# RiskChemi_Monitor_V1_05M1.net
KiCad netlist of a schematic drawn in Altium Designer
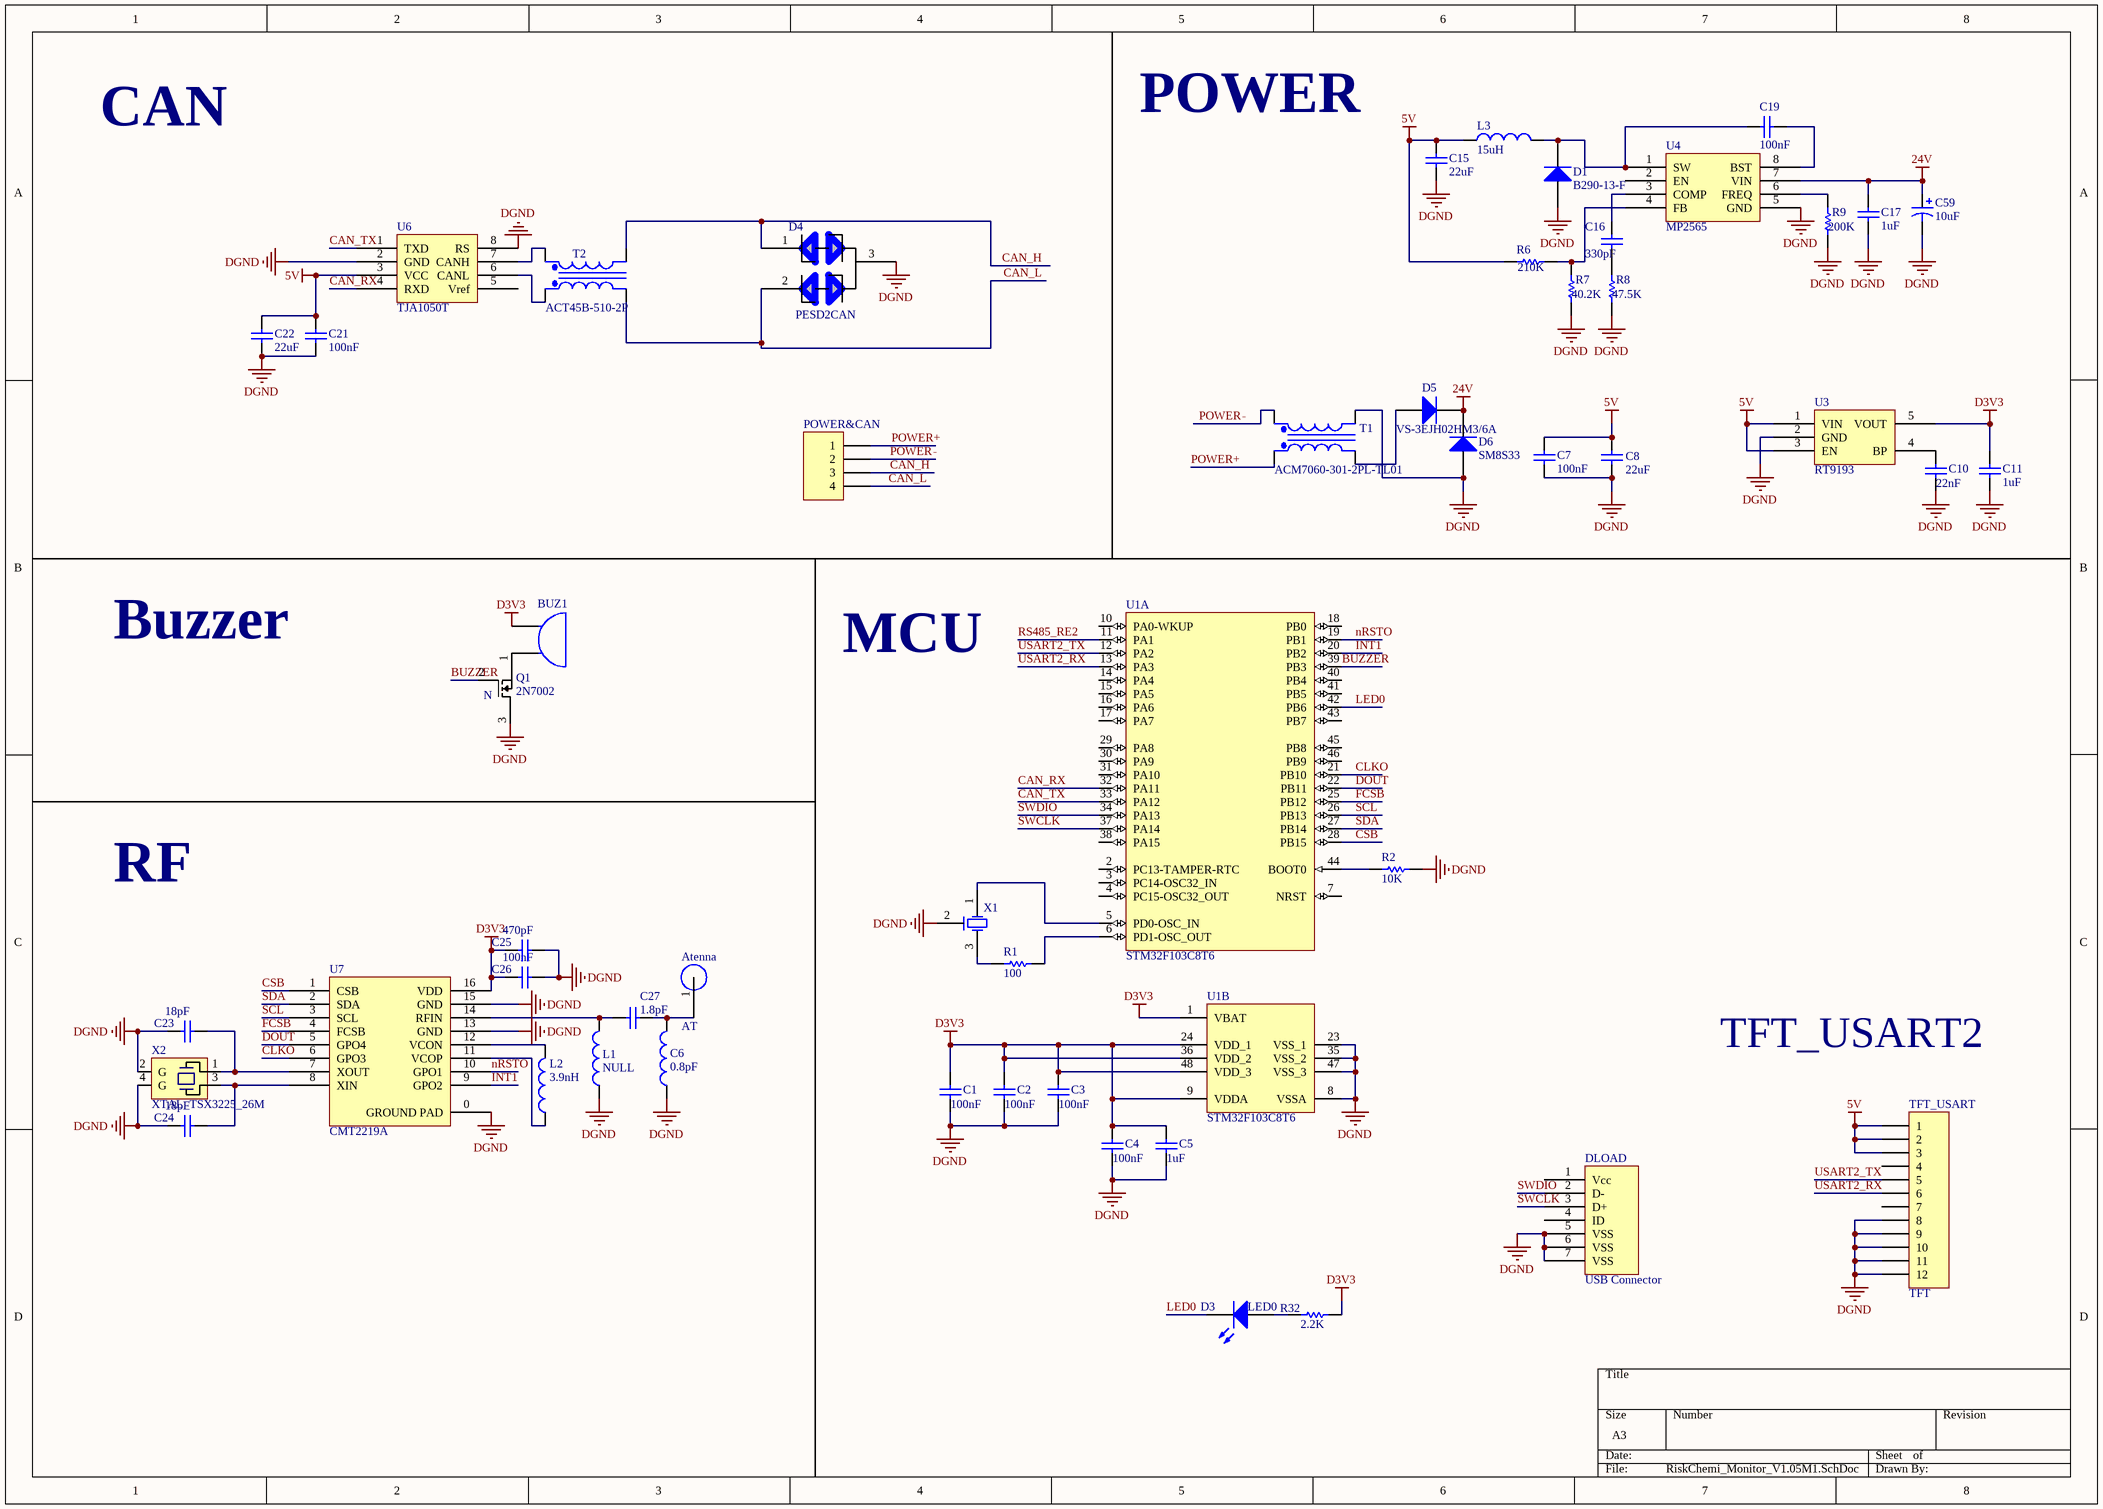
[diagram p0: RiskChemi_Monitor_V1.05M1.SchDoc]

(export (version "E")
  (design (tool "Eeschema 10.0.6"))
  (components
    (comp (ref "Atenna") (value "AT") (footprint "433MHz Atenna") (libsource (lib "MySchlib1") (part "AT")))
    (comp (ref "BUZ1")
      (value "BUZZER")
      (footprint "BUZ0905")
      (description "Buzzer")
      (libsource (lib "杂元件库") (part "BUZZER"))
    )
    (comp (ref "C1")
      (value "100nF")
      (footprint "0603")
      (description "Capacitor")
      (fields (field (name "PUBLISHER") "Altium Limited"))
      (libsource (lib "Miscellaneous Devices") (part "Cap"))
    )
    (comp (ref "C2")
      (value "100nF")
      (footprint "0603")
      (description "Capacitor")
      (fields (field (name "PUBLISHER") "Altium Limited"))
      (libsource (lib "Miscellaneous Devices") (part "Cap"))
    )
    (comp (ref "C3")
      (value "100nF")
      (footprint "0603")
      (description "Capacitor")
      (fields (field (name "PUBLISHER") "Altium Limited"))
      (libsource (lib "Miscellaneous Devices") (part "Cap"))
    )
    (comp (ref "C4")
      (value "100nF")
      (footprint "0603")
      (description "Capacitor")
      (fields (field (name "PUBLISHER") "Altium Limited"))
      (libsource (lib "Miscellaneous Devices") (part "Cap"))
    )
    (comp (ref "C5")
      (value "1uF")
      (footprint "0603")
      (description "Capacitor")
      (fields (field (name "PUBLISHER") "Altium Limited"))
      (libsource (lib "Miscellaneous Devices") (part "Cap"))
    )
    (comp (ref "C6")
      (value "0.8pF")
      (footprint "Miscellaneous Devices:0402")
      (description "Inductor")
      (fields (field (name "PUBLISHER") "Altium Limited"))
      (libsource (lib "Miscellaneous Devices") (part "Inductor"))
    )
    (comp (ref "C7")
      (value "100nF")
      (footprint "0805")
      (description "Capacitor,100V")
      (fields (field (name "PUBLISHER") "Altium Limited"))
      (libsource (lib "Miscellaneous Devices") (part "Cap"))
    )
    (comp (ref "C8")
      (value "22uF")
      (footprint "0805")
      (description "Capacitor")
      (fields (field (name "PUBLISHER") "Altium Limited"))
      (libsource (lib "Miscellaneous Devices") (part "Cap"))
    )
    (comp (ref "C10")
      (value "22nF")
      (footprint "BinFeng:0603")
      (description "Capacitor")
      (fields (field (name "PUBLISHER") "Altium Limited"))
      (libsource (lib "Miscellaneous Devices") (part "Cap"))
    )
    (comp (ref "C11")
      (value "1uF")
      (footprint "BinFeng:0603")
      (description "Capacitor")
      (fields (field (name "PUBLISHER") "Altium Limited"))
      (libsource (lib "Miscellaneous Devices") (part "Cap"))
    )
    (comp (ref "C15")
      (value "22uF")
      (footprint "0805")
      (description "Capacitor,50V")
      (fields (field (name "PUBLISHER") "Altium Limited"))
      (libsource (lib "Miscellaneous Devices") (part "Cap"))
    )
    (comp (ref "C16")
      (value "330pF")
      (footprint "BinFeng:0402")
      (description "Capacitor")
      (fields (field (name "PUBLISHER") "Altium Limited"))
      (libsource (lib "Miscellaneous Devices") (part "Cap"))
    )
    (comp (ref "C17")
      (value "1uF")
      (footprint "0805")
      (description "Capacitor,100V")
      (fields (field (name "PUBLISHER") "Altium Limited"))
      (libsource (lib "Miscellaneous Devices") (part "Cap"))
    )
    (comp (ref "C19")
      (value "100nF")
      (footprint "BinFeng:0402")
      (description "Capacitor")
      (fields (field (name "PUBLISHER") "Altium Limited"))
      (libsource (lib "Miscellaneous Devices") (part "Cap"))
    )
    (comp (ref "C21")
      (value "100nF")
      (footprint "0603")
      (description "Capacitor")
      (fields (field (name "PUBLISHER") "Altium Limited"))
      (libsource (lib "Miscellaneous Devices") (part "Cap"))
    )
    (comp (ref "C22")
      (value "22uF")
      (footprint "0805")
      (description "Capacitor")
      (fields (field (name "PUBLISHER") "Altium Limited"))
      (libsource (lib "Miscellaneous Devices") (part "Cap"))
    )
    (comp (ref "C23")
      (value "18pF")
      (footprint "BinFeng:0402")
      (description "Capacitor")
      (fields (field (name "PUBLISHER") "Altium Limited"))
      (libsource (lib "Miscellaneous Devices") (part "Cap"))
    )
    (comp (ref "C24")
      (value "18pF")
      (footprint "BinFeng:0402")
      (description "Capacitor")
      (fields (field (name "PUBLISHER") "Altium Limited"))
      (libsource (lib "Miscellaneous Devices") (part "Cap"))
    )
    (comp (ref "C25")
      (value "470pF")
      (footprint "BinFeng:0402")
      (description "Capacitor")
      (fields (field (name "PUBLISHER") "Altium Limited"))
      (libsource (lib "Miscellaneous Devices") (part "Cap"))
    )
    (comp (ref "C26")
      (value "100nF")
      (footprint "BinFeng:0603")
      (description "Capacitor")
      (fields (field (name "PUBLISHER") "Altium Limited"))
      (libsource (lib "Miscellaneous Devices") (part "Cap"))
    )
    (comp (ref "C27")
      (value "1.8pF")
      (footprint "BinFeng:nosilk_0402")
      (description "Capacitor")
      (fields (field (name "PUBLISHER") "Altium Limited"))
      (libsource (lib "Miscellaneous Devices") (part "Cap"))
    )
    (comp (ref "C59")
      (value "10uF")
      (footprint "6032_pol")
      (description "Polarized Capacitor (Radial)")
      (fields (field (name "PUBLISHER") "Altium Limited"))
      (libsource (lib "Miscellaneous Devices") (part "Cap Pol1"))
    )
    (comp (ref "D1")
      (value "B290-13-F")
      (footprint "back:B290")
      (description "Default Diode")
      (fields (field (name "PUBLISHER") "Altium Limited"))
      (libsource (lib "Miscellaneous Devices") (part "Diode"))
    )
    (comp (ref "D3")
      (value "LED0")
      (footprint "LED")
      (description "green LED")
      (fields (field (name "PUBLISHER") "Altium Limited"))
      (libsource (lib "Miscellaneous Devices") (part "LED0"))
    )
    (comp (ref "D4")
      (value "PESD2CAN")
      (footprint "SOT23")
      (libsource (lib "BinFeng_Connectors") (part "PESD1CAN"))
    )
    (comp (ref "D5")
      (value "VS-3EJH02HM3/6A")
      (footprint "back:B290")
      (description "1 Amp General Purpose Rectifier")
      (fields (field (name "PUBLISHER") "Altium Limited"))
      (libsource (lib "Miscellaneous Devices") (part "Diode 1N4007"))
    )
    (comp (ref "D6")
      (value "SM8S33")
      (footprint "SM8S")
      (description "1 Amp General Purpose Rectifier")
      (fields (field (name "PUBLISHER") "Altium Limited"))
      (libsource (lib "Miscellaneous Devices") (part "Diode 1N4007"))
    )
    (comp (ref "DLOAD")
      (value "USB Connector")
      (footprint "Mini_USB")
      (libsource (lib "BinFeng_Connectors") (part "Component_1"))
    )
    (comp (ref "L1")
      (value "NULL")
      (footprint "Miscellaneous Devices:0402")
      (description "Inductor")
      (fields (field (name "PUBLISHER") "Altium Limited"))
      (libsource (lib "Miscellaneous Devices") (part "Inductor"))
    )
    (comp (ref "L2")
      (value "3.9nH")
      (footprint "BinFeng:0603")
      (description "Inductor")
      (fields (field (name "PUBLISHER") "Altium Limited"))
      (libsource (lib "Miscellaneous Devices") (part "Inductor"))
    )
    (comp (ref "L3")
      (value "15uH")
      (footprint "4*4 Inductor")
      (description "Inductor, 1A")
      (fields (field (name "PUBLISHER") "Altium Limited"))
      (libsource (lib "Miscellaneous Devices") (part "Inductor"))
    )
    (comp (ref "POWER&CAN")
      (value "Header 4")
      (footprint "hg:Wafer 4pin")
      (description "Header, 4-Pin")
      (fields (field (name "PUBLISHER") "Altium Limited"))
      (libsource (lib "Miscellaneous Connectors") (part "Header 4"))
    )
    (comp (ref "Q1") (value "2N7002") (footprint "2N7002") (libsource (lib "seeder") (part "N-MOSFET")))
    (comp (ref "R1")
      (value "100")
      (footprint "back:0603")
      (description "Resistor")
      (fields (field (name "PUBLISHER") "Altium Limited"))
      (libsource (lib "Miscellaneous Devices") (part "Res1"))
    )
    (comp (ref "R2")
      (value "10K")
      (footprint "back:0603")
      (description "Resistor")
      (fields (field (name "PUBLISHER") "Altium Limited"))
      (libsource (lib "Miscellaneous Devices") (part "Res1"))
    )
    (comp (ref "R6")
      (value "210K")
      (footprint "BinFeng:0402")
      (description "Resistor")
      (fields (field (name "PUBLISHER") "Altium Limited"))
      (libsource (lib "Miscellaneous Devices") (part "Res1"))
    )
    (comp (ref "R7")
      (value "40.2K")
      (footprint "BinFeng:0402")
      (description "Resistor")
      (fields (field (name "PUBLISHER") "Altium Limited"))
      (libsource (lib "Miscellaneous Devices") (part "Res1"))
    )
    (comp (ref "R8")
      (value "47.5K")
      (footprint "BinFeng:0402")
      (description "Resistor")
      (fields (field (name "PUBLISHER") "Altium Limited"))
      (libsource (lib "Miscellaneous Devices") (part "Res1"))
    )
    (comp (ref "R9")
      (value "200K")
      (footprint "BinFeng:0402")
      (description "Resistor")
      (fields (field (name "PUBLISHER") "Altium Limited"))
      (libsource (lib "Miscellaneous Devices") (part "Res1"))
    )
    (comp (ref "R32")
      (value "2.2K")
      (footprint "BinFeng:0603")
      (description "Resistor")
      (fields (field (name "PUBLISHER") "Altium Limited"))
      (libsource (lib "Miscellaneous Devices") (part "Res1"))
    )
    (comp (ref "T1")
      (value "ACM7060-301-2PL-TL01")
      (footprint "ACM7060-301-2P-TL01")
      (description "Transformer (Equivalent Circuit Model)")
      (fields (field (name "PUBLISHER") "Altium Limited"))
      (libsource (lib "Miscellaneous Devices") (part "Trans Eq"))
    )
    (comp (ref "T2")
      (value "ACT45B-510-2P")
      (footprint "ACT45B-510-2P")
      (description "Transformer (Equivalent Circuit Model)")
      (fields (field (name "PUBLISHER") "Altium Limited"))
      (libsource (lib "Miscellaneous Devices") (part "Trans Eq"))
    )
    (comp (ref "TFT_USART")
      (value "TFT")
      (footprint "FCC_10pin_1mm")
      (description "Header, 12-Pin")
      (fields (field (name "PUBLISHER") "Altium Limited"))
      (libsource (lib "Miscellaneous Connectors") (part "Header 12"))
    )
    (comp (ref "U1")
      (value "STM32F103C8T6")
      (footprint "STM-LQFP48_N")
      (libsource (lib "STMicroelectronics STM32 F1") (part "STM32F103C8T6"))
    )
    (comp (ref "U3") (value "RT9193") (footprint "SOT-23-5") (libsource (lib "BinFeng_IC") (part "RT9193")))
    (comp (ref "U4")
      (value "MP2565")
      (footprint "SO8")
      (description "DCDC 4.5V~28V input 1.8V ~5V output low power")
      (libsource (lib "BinFeng_IC") (part "MP1584"))
    )
    (comp (ref "U6")
      (value "TJA1050T")
      (footprint "SO8")
      (description "CAN Tranceiver")
      (libsource (lib "BinFeng_IC") (part "TJA1050T"))
    )
    (comp (ref "U7")
      (value "CMT2219A")
      (footprint "back:QFN16")
      (libsource (lib "BinFeng_IC") (part "CMT2219A"))
    )
    (comp (ref "X1") (value "8M smd") (footprint "8Mhz_XTAL") (libsource (lib "Schlib1") (part "8M smd")))
    (comp (ref "X2")
      (value "XTAL_TSX3225_26M")
      (footprint "XTAL3225")
      (libsource (lib "BinFeng_IC") (part "XTAL_Negative"))
    )
  )
  (nets
    (net (code "1") (name "/BUZZER") (class "Default")
      (node (ref "Q1") (pin "2") (pinfunction "G_2") (pintype "passive"))
      (node (ref "U1") (pin "39") (pinfunction "PB3_39") (pintype "bidirectional"))
    )
    (net (code "2") (name "/CAN_H") (class "Default")
      (node (ref "D4") (pin "1") (pinfunction "11_1") (pintype "passive"))
      (node (ref "POWER&CAN") (pin "3") (pinfunction "3_3") (pintype "passive"))
      (node (ref "T2") (pin "4") (pinfunction "Sec-_4") (pintype "passive"))
    )
    (net (code "3") (name "/CAN_L") (class "Default")
      (node (ref "D4") (pin "2") (pinfunction "12_2") (pintype "passive"))
      (node (ref "POWER&CAN") (pin "4") (pinfunction "4_4") (pintype "passive"))
      (node (ref "T2") (pin "2") (pinfunction "Pri-_2") (pintype "passive"))
    )
    (net (code "4") (name "/CAN_RX") (class "Default")
      (node (ref "U1") (pin "32") (pinfunction "PA11_32") (pintype "bidirectional"))
      (node (ref "U6") (pin "4") (pinfunction "RXD_4") (pintype "passive"))
    )
    (net (code "5") (name "/CAN_TX") (class "Default")
      (node (ref "U1") (pin "33") (pinfunction "PA12_33") (pintype "bidirectional"))
      (node (ref "U6") (pin "1") (pinfunction "TXD_1") (pintype "passive"))
    )
    (net (code "6") (name "/CLKO") (class "Default")
      (node (ref "U1") (pin "21") (pinfunction "PB10_21") (pintype "bidirectional"))
      (node (ref "U7") (pin "6") (pinfunction "GPO3_6") (pintype "passive"))
    )
    (net (code "7") (name "/CSB") (class "Default")
      (node (ref "U1") (pin "28") (pinfunction "PB15_28") (pintype "bidirectional"))
      (node (ref "U7") (pin "1") (pinfunction "CSB_1") (pintype "passive"))
    )
    (net (code "8") (name "/DOUT") (class "Default")
      (node (ref "U1") (pin "22") (pinfunction "PB11_22") (pintype "bidirectional"))
      (node (ref "U7") (pin "5") (pinfunction "GPO4_5") (pintype "passive"))
    )
    (net (code "9") (name "/FCSB") (class "Default")
      (node (ref "U1") (pin "25") (pinfunction "PB12_25") (pintype "bidirectional"))
      (node (ref "U7") (pin "4") (pinfunction "FCSB_4") (pintype "passive"))
    )
    (net (code "10") (name "/INT1") (class "Default")
      (node (ref "U1") (pin "20") (pinfunction "PB2_20") (pintype "bidirectional"))
      (node (ref "U7") (pin "9") (pinfunction "GPO2_9") (pintype "passive"))
    )
    (net (code "11") (name "/LED0") (class "Default")
      (node (ref "D3") (pin "2") (pinfunction "K_2") (pintype "passive"))
      (node (ref "U1") (pin "42") (pinfunction "PB6_42") (pintype "bidirectional"))
    )
    (net (code "12") (name "/POWER+") (class "Default")
      (node (ref "POWER&CAN") (pin "1") (pinfunction "1_1") (pintype "passive"))
      (node (ref "T1") (pin "1") (pinfunction "Pri+_1") (pintype "passive"))
    )
    (net (code "13") (name "/POWER﹣") (class "Default")
      (node (ref "POWER&CAN") (pin "2") (pinfunction "2_2") (pintype "passive"))
      (node (ref "T1") (pin "3") (pinfunction "Sec+_3") (pintype "passive"))
    )
    (net (code "14") (name "/RS485_RE2") (class "Default")
      (node (ref "U1") (pin "11") (pinfunction "PA1_11") (pintype "bidirectional"))
    )
    (net (code "15") (name "/SCL") (class "Default")
      (node (ref "U1") (pin "26") (pinfunction "PB13_26") (pintype "bidirectional"))
      (node (ref "U7") (pin "3") (pinfunction "SCL_3") (pintype "passive"))
    )
    (net (code "16") (name "/SDA") (class "Default")
      (node (ref "U1") (pin "27") (pinfunction "PB14_27") (pintype "bidirectional"))
      (node (ref "U7") (pin "2") (pinfunction "SDA_2") (pintype "passive"))
    )
    (net (code "17") (name "/SWCLK") (class "Default")
      (node (ref "DLOAD") (pin "3") (pinfunction "D+_3") (pintype "passive"))
      (node (ref "U1") (pin "37") (pinfunction "PA14_37") (pintype "bidirectional"))
    )
    (net (code "18") (name "/SWDIO") (class "Default")
      (node (ref "DLOAD") (pin "2") (pinfunction "D-_2") (pintype "passive"))
      (node (ref "U1") (pin "34") (pinfunction "PA13_34") (pintype "bidirectional"))
    )
    (net (code "19") (name "/USART2_RX") (class "Default")
      (node (ref "TFT_USART") (pin "6") (pinfunction "6_6") (pintype "passive"))
      (node (ref "U1") (pin "13") (pinfunction "PA3_13") (pintype "bidirectional"))
    )
    (net (code "20") (name "/USART2_TX") (class "Default")
      (node (ref "TFT_USART") (pin "5") (pinfunction "5_5") (pintype "passive"))
      (node (ref "U1") (pin "12") (pinfunction "PA2_12") (pintype "bidirectional"))
    )
    (net (code "21") (name "/nRSTO") (class "Default")
      (node (ref "U1") (pin "19") (pinfunction "PB1_19") (pintype "bidirectional"))
      (node (ref "U7") (pin "10") (pinfunction "GPO1_10") (pintype "passive"))
    )
    (net (code "22") (name "5V") (class "Default")
      (node (ref "C15") (pin "2") (pinfunction "2_2") (pintype "passive"))
      (node (ref "C21") (pin "1") (pinfunction "1_1") (pintype "passive"))
      (node (ref "C22") (pin "2") (pinfunction "2_2") (pintype "passive"))
      (node (ref "C7") (pin "2") (pinfunction "2_2") (pintype "passive"))
      (node (ref "C8") (pin "2") (pinfunction "2_2") (pintype "passive"))
      (node (ref "L3") (pin "1") (pinfunction "1_1") (pintype "passive"))
      (node (ref "R6") (pin "2") (pinfunction "2_2") (pintype "passive"))
      (node (ref "TFT_USART") (pin "1") (pinfunction "1_1") (pintype "passive"))
      (node (ref "TFT_USART") (pin "2") (pinfunction "2_2") (pintype "passive"))
      (node (ref "TFT_USART") (pin "3") (pinfunction "3_3") (pintype "passive"))
      (node (ref "U3") (pin "1") (pinfunction "VIN_1") (pintype "passive"))
      (node (ref "U3") (pin "3") (pinfunction "EN_3") (pintype "passive"))
      (node (ref "U6") (pin "3") (pinfunction "VCC_3") (pintype "passive"))
    )
    (net (code "23") (name "24V") (class "Default")
      (node (ref "C17") (pin "2") (pinfunction "2_2") (pintype "passive"))
      (node (ref "C59") (pin "1") (pinfunction "1_1") (pintype "passive"))
      (node (ref "D5") (pin "2") (pinfunction "K_2") (pintype "passive"))
      (node (ref "D6") (pin "2") (pinfunction "K_2") (pintype "passive"))
      (node (ref "U4") (pin "7") (pinfunction "VIN_7") (pintype "passive"))
    )
    (net (code "24") (name "D3V3") (class "Default")
      (node (ref "BUZ1") (pin "1") (pinfunction "A_1") (pintype "passive"))
      (node (ref "C1") (pin "2") (pinfunction "2_2") (pintype "passive"))
      (node (ref "C11") (pin "2") (pinfunction "2_2") (pintype "passive"))
      (node (ref "C2") (pin "2") (pinfunction "2_2") (pintype "passive"))
      (node (ref "C25") (pin "2") (pinfunction "2_2") (pintype "passive"))
      (node (ref "C26") (pin "2") (pinfunction "2_2") (pintype "passive"))
      (node (ref "C3") (pin "2") (pinfunction "2_2") (pintype "passive"))
      (node (ref "C4") (pin "2") (pinfunction "2_2") (pintype "passive"))
      (node (ref "C5") (pin "2") (pinfunction "2_2") (pintype "passive"))
      (node (ref "R32") (pin "1") (pinfunction "1_1") (pintype "passive"))
      (node (ref "U1") (pin "1") (pinfunction "VBAT_1") (pintype "power_in"))
      (node (ref "U1") (pin "24") (pinfunction "VDD_1_24") (pintype "power_in"))
      (node (ref "U1") (pin "36") (pinfunction "VDD_2_36") (pintype "power_in"))
      (node (ref "U1") (pin "48") (pinfunction "VDD_3_48") (pintype "power_in"))
      (node (ref "U1") (pin "9") (pinfunction "VDDA_9") (pintype "power_in"))
      (node (ref "U3") (pin "5") (pinfunction "VOUT_5") (pintype "passive"))
      (node (ref "U7") (pin "16") (pinfunction "VDD_16") (pintype "passive"))
    )
    (net (code "25") (name "DGND") (class "Default")
      (node (ref "C1") (pin "1") (pinfunction "1_1") (pintype "passive"))
      (node (ref "C10") (pin "1") (pinfunction "1_1") (pintype "passive"))
      (node (ref "C11") (pin "1") (pinfunction "1_1") (pintype "passive"))
      (node (ref "C15") (pin "1") (pinfunction "1_1") (pintype "passive"))
      (node (ref "C17") (pin "1") (pinfunction "1_1") (pintype "passive"))
      (node (ref "C2") (pin "1") (pinfunction "1_1") (pintype "passive"))
      (node (ref "C21") (pin "2") (pinfunction "2_2") (pintype "passive"))
      (node (ref "C22") (pin "1") (pinfunction "1_1") (pintype "passive"))
      (node (ref "C23") (pin "2") (pinfunction "2_2") (pintype "passive"))
      (node (ref "C24") (pin "2") (pinfunction "2_2") (pintype "passive"))
      (node (ref "C25") (pin "1") (pinfunction "1_1") (pintype "passive"))
      (node (ref "C26") (pin "1") (pinfunction "1_1") (pintype "passive"))
      (node (ref "C3") (pin "1") (pinfunction "1_1") (pintype "passive"))
      (node (ref "C4") (pin "1") (pinfunction "1_1") (pintype "passive"))
      (node (ref "C5") (pin "1") (pinfunction "1_1") (pintype "passive"))
      (node (ref "C59") (pin "2") (pinfunction "2_2") (pintype "passive"))
      (node (ref "C6") (pin "1") (pinfunction "1_1") (pintype "passive"))
      (node (ref "C7") (pin "1") (pinfunction "1_1") (pintype "passive"))
      (node (ref "C8") (pin "1") (pinfunction "1_1") (pintype "passive"))
      (node (ref "D1") (pin "1") (pinfunction "A_1") (pintype "passive"))
      (node (ref "D4") (pin "3") (pinfunction "13_3") (pintype "passive"))
      (node (ref "D6") (pin "1") (pinfunction "A_1") (pintype "passive"))
      (node (ref "DLOAD") (pin "5") (pinfunction "VSS_5") (pintype "passive"))
      (node (ref "DLOAD") (pin "6") (pinfunction "VSS_6") (pintype "passive"))
      (node (ref "DLOAD") (pin "7") (pinfunction "VSS_7") (pintype "passive"))
      (node (ref "L1") (pin "1") (pinfunction "1_1") (pintype "passive"))
      (node (ref "Q1") (pin "3") (pinfunction "S_3") (pintype "passive"))
      (node (ref "R2") (pin "2") (pinfunction "2_2") (pintype "passive"))
      (node (ref "R7") (pin "1") (pinfunction "1_1") (pintype "passive"))
      (node (ref "R8") (pin "1") (pinfunction "1_1") (pintype "passive"))
      (node (ref "R9") (pin "1") (pinfunction "1_1") (pintype "passive"))
      (node (ref "T1") (pin "4") (pinfunction "Sec-_4") (pintype "passive"))
      (node (ref "TFT_USART") (pin "10") (pinfunction "10_10") (pintype "passive"))
      (node (ref "TFT_USART") (pin "11") (pinfunction "11_11") (pintype "passive"))
      (node (ref "TFT_USART") (pin "12") (pinfunction "12_12") (pintype "passive"))
      (node (ref "TFT_USART") (pin "8") (pinfunction "8_8") (pintype "passive"))
      (node (ref "TFT_USART") (pin "9") (pinfunction "9_9") (pintype "passive"))
      (node (ref "U1") (pin "23") (pinfunction "VSS_1_23") (pintype "power_in"))
      (node (ref "U1") (pin "35") (pinfunction "VSS_2_35") (pintype "power_in"))
      (node (ref "U1") (pin "47") (pinfunction "VSS_3_47") (pintype "power_in"))
      (node (ref "U1") (pin "8") (pinfunction "VSSA_8") (pintype "power_in"))
      (node (ref "U3") (pin "2") (pinfunction "GND_2") (pintype "passive"))
      (node (ref "U4") (pin "5") (pinfunction "GND_5") (pintype "passive"))
      (node (ref "U6") (pin "2") (pinfunction "GND_2") (pintype "passive"))
      (node (ref "U6") (pin "8") (pinfunction "RS_8") (pintype "passive"))
      (node (ref "U7") (pin "0") (pinfunction "GROUND_PAD_0") (pintype "passive"))
      (node (ref "U7") (pin "13") (pinfunction "GND_13") (pintype "passive"))
      (node (ref "U7") (pin "15") (pinfunction "GND_15") (pintype "passive"))
      (node (ref "X1") (pin "2") (pinfunction "GND_2") (pintype "passive"))
      (node (ref "X2") (pin "2") (pinfunction "G_2") (pintype "passive"))
      (node (ref "X2") (pin "4") (pinfunction "G_4") (pintype "passive"))
    )
    (net (code "26") (name "Net-(Atenna-Pad1)") (class "Default")
      (node (ref "Atenna") (pin "1") (pinfunction "1_1") (pintype "passive"))
      (node (ref "C27") (pin "1") (pinfunction "1_1") (pintype "passive"))
      (node (ref "C6") (pin "2") (pinfunction "2_2") (pintype "passive"))
    )
    (net (code "27") (name "Net-(BUZ1-B)") (class "Default")
      (node (ref "BUZ1") (pin "2") (pinfunction "B_2") (pintype "passive"))
      (node (ref "Q1") (pin "1") (pinfunction "D_1") (pintype "passive"))
    )
    (net (code "28") (name "Net-(C16-Pad2)") (class "Default")
      (node (ref "C16") (pin "2") (pinfunction "2_2") (pintype "passive"))
      (node (ref "R8") (pin "2") (pinfunction "2_2") (pintype "passive"))
    )
    (net (code "29") (name "Net-(D1-K)") (class "Default")
      (node (ref "C19") (pin "2") (pinfunction "2_2") (pintype "passive"))
      (node (ref "D1") (pin "2") (pinfunction "K_2") (pintype "passive"))
      (node (ref "L3") (pin "2") (pinfunction "2_2") (pintype "passive"))
      (node (ref "U4") (pin "1") (pinfunction "SW_1") (pintype "passive"))
    )
    (net (code "30") (name "Net-(D3-A)") (class "Default")
      (node (ref "D3") (pin "1") (pinfunction "A_1") (pintype "passive"))
      (node (ref "R32") (pin "2") (pinfunction "2_2") (pintype "passive"))
    )
    (net (code "31") (name "Net-(D5-A)") (class "Default")
      (node (ref "D5") (pin "1") (pinfunction "A_1") (pintype "passive"))
      (node (ref "T1") (pin "2") (pinfunction "Pri-_2") (pintype "passive"))
    )
    (net (code "32") (name "Net-(T2-Pri+)") (class "Default")
      (node (ref "T2") (pin "1") (pinfunction "Pri+_1") (pintype "passive"))
      (node (ref "U6") (pin "6") (pinfunction "CANL_6") (pintype "passive"))
    )
    (net (code "33") (name "Net-(T2-Sec+)") (class "Default")
      (node (ref "T2") (pin "3") (pinfunction "Sec+_3") (pintype "passive"))
      (node (ref "U6") (pin "7") (pinfunction "CANH_7") (pintype "passive"))
    )
    (net (code "34") (name "Net-(U1A-BOOT0)") (class "Default")
      (node (ref "R2") (pin "1") (pinfunction "1_1") (pintype "passive"))
      (node (ref "U1") (pin "44") (pinfunction "BOOT0_44") (pintype "input"))
    )
    (net (code "35") (name "Net-(U1A-PD0-OSC_IN)") (class "Default")
      (node (ref "U1") (pin "5") (pinfunction "PD0-OSC_IN_5") (pintype "bidirectional"))
      (node (ref "X1") (pin "1") (pinfunction "OSC1_1") (pintype "passive"))
    )
    (net (code "36") (name "Net-(U1A-PD1-OSC_OUT)") (class "Default")
      (node (ref "R1") (pin "2") (pinfunction "2_2") (pintype "passive"))
      (node (ref "U1") (pin "6") (pinfunction "PD1-OSC_OUT_6") (pintype "bidirectional"))
    )
    (net (code "37") (name "Net-(U3-BP)") (class "Default")
      (node (ref "C10") (pin "2") (pinfunction "2_2") (pintype "passive"))
      (node (ref "U3") (pin "4") (pinfunction "BP_4") (pintype "passive"))
    )
    (net (code "38") (name "Net-(U4-BST)") (class "Default")
      (node (ref "C19") (pin "1") (pinfunction "1_1") (pintype "passive"))
      (node (ref "U4") (pin "8") (pinfunction "BST_8") (pintype "passive"))
    )
    (net (code "39") (name "Net-(U4-COMP)") (class "Default")
      (node (ref "C16") (pin "1") (pinfunction "1_1") (pintype "passive"))
      (node (ref "U4") (pin "3") (pinfunction "COMP_3") (pintype "passive"))
    )
    (net (code "40") (name "Net-(U4-FB)") (class "Default")
      (node (ref "R6") (pin "1") (pinfunction "1_1") (pintype "passive"))
      (node (ref "R7") (pin "2") (pinfunction "2_2") (pintype "passive"))
      (node (ref "U4") (pin "4") (pinfunction "FB_4") (pintype "passive"))
    )
    (net (code "41") (name "Net-(U4-FREQ)") (class "Default")
      (node (ref "R9") (pin "2") (pinfunction "2_2") (pintype "passive"))
      (node (ref "U4") (pin "6") (pinfunction "FREQ_6") (pintype "passive"))
    )
    (net (code "42") (name "Net-(U7-RFIN)") (class "Default")
      (node (ref "C27") (pin "2") (pinfunction "2_2") (pintype "passive"))
      (node (ref "L1") (pin "2") (pinfunction "2_2") (pintype "passive"))
      (node (ref "U7") (pin "14") (pinfunction "RFIN_14") (pintype "passive"))
    )
    (net (code "43") (name "Net-(U7-VCON)") (class "Default")
      (node (ref "L2") (pin "2") (pinfunction "2_2") (pintype "passive"))
      (node (ref "U7") (pin "12") (pinfunction "VCON_12") (pintype "passive"))
    )
    (net (code "44") (name "Net-(U7-VCOP)") (class "Default")
      (node (ref "L2") (pin "1") (pinfunction "1_1") (pintype "passive"))
      (node (ref "U7") (pin "11") (pinfunction "VCOP_11") (pintype "passive"))
    )
    (net (code "45") (name "Net-(U7-XIN)") (class "Default")
      (node (ref "C24") (pin "1") (pinfunction "1_1") (pintype "passive"))
      (node (ref "U7") (pin "8") (pinfunction "XIN_8") (pintype "passive"))
      (node (ref "X2") (pin "3") (pintype "passive"))
    )
    (net (code "46") (name "Net-(U7-XOUT)") (class "Default")
      (node (ref "C23") (pin "1") (pinfunction "1_1") (pintype "passive"))
      (node (ref "U7") (pin "7") (pinfunction "XOUT_7") (pintype "passive"))
      (node (ref "X2") (pin "1") (pintype "passive"))
    )
    (net (code "47") (name "Net-(X1-OSC2)") (class "Default")
      (node (ref "R1") (pin "1") (pinfunction "1_1") (pintype "passive"))
      (node (ref "X1") (pin "3") (pinfunction "OSC2_3") (pintype "passive"))
    )
    (net (code "48") (name "unconnected-(DLOAD-ID-Pad4)") (class "Default")
      (node (ref "DLOAD") (pin "4") (pinfunction "ID_4") (pintype "passive"))
    )
    (net (code "49") (name "unconnected-(DLOAD-Vcc-Pad1)") (class "Default")
      (node (ref "DLOAD") (pin "1") (pinfunction "Vcc_1") (pintype "passive"))
    )
    (net (code "50") (name "unconnected-(TFT_USART-Pad4)") (class "Default")
      (node (ref "TFT_USART") (pin "4") (pinfunction "4_4") (pintype "passive"))
    )
    (net (code "51") (name "unconnected-(TFT_USART-Pad7)") (class "Default")
      (node (ref "TFT_USART") (pin "7") (pinfunction "7_7") (pintype "passive"))
    )
    (net (code "52") (name "unconnected-(U1A-NRST-Pad7)") (class "Default")
      (node (ref "U1") (pin "7") (pinfunction "NRST_7") (pintype "bidirectional"))
    )
    (net (code "53") (name "unconnected-(U1A-PA0-WKUP-Pad10)") (class "Default")
      (node (ref "U1") (pin "10") (pinfunction "PA0-WKUP_10") (pintype "bidirectional"))
    )
    (net (code "54") (name "unconnected-(U1A-PA4-Pad14)") (class "Default")
      (node (ref "U1") (pin "14") (pinfunction "PA4_14") (pintype "bidirectional"))
    )
    (net (code "55") (name "unconnected-(U1A-PA5-Pad15)") (class "Default")
      (node (ref "U1") (pin "15") (pinfunction "PA5_15") (pintype "bidirectional"))
    )
    (net (code "56") (name "unconnected-(U1A-PA6-Pad16)") (class "Default")
      (node (ref "U1") (pin "16") (pinfunction "PA6_16") (pintype "bidirectional"))
    )
    (net (code "57") (name "unconnected-(U1A-PA7-Pad17)") (class "Default")
      (node (ref "U1") (pin "17") (pinfunction "PA7_17") (pintype "bidirectional"))
    )
    (net (code "58") (name "unconnected-(U1A-PA8-Pad29)") (class "Default")
      (node (ref "U1") (pin "29") (pinfunction "PA8_29") (pintype "bidirectional"))
    )
    (net (code "59") (name "unconnected-(U1A-PA9-Pad30)") (class "Default")
      (node (ref "U1") (pin "30") (pinfunction "PA9_30") (pintype "bidirectional"))
    )
    (net (code "60") (name "unconnected-(U1A-PA10-Pad31)") (class "Default")
      (node (ref "U1") (pin "31") (pinfunction "PA10_31") (pintype "bidirectional"))
    )
    (net (code "61") (name "unconnected-(U1A-PA15-Pad38)") (class "Default")
      (node (ref "U1") (pin "38") (pinfunction "PA15_38") (pintype "bidirectional"))
    )
    (net (code "62") (name "unconnected-(U1A-PB0-Pad18)") (class "Default")
      (node (ref "U1") (pin "18") (pinfunction "PB0_18") (pintype "bidirectional"))
    )
    (net (code "63") (name "unconnected-(U1A-PB4-Pad40)") (class "Default")
      (node (ref "U1") (pin "40") (pinfunction "PB4_40") (pintype "bidirectional"))
    )
    (net (code "64") (name "unconnected-(U1A-PB5-Pad41)") (class "Default")
      (node (ref "U1") (pin "41") (pinfunction "PB5_41") (pintype "bidirectional"))
    )
    (net (code "65") (name "unconnected-(U1A-PB7-Pad43)") (class "Default")
      (node (ref "U1") (pin "43") (pinfunction "PB7_43") (pintype "bidirectional"))
    )
    (net (code "66") (name "unconnected-(U1A-PB8-Pad45)") (class "Default")
      (node (ref "U1") (pin "45") (pinfunction "PB8_45") (pintype "bidirectional"))
    )
    (net (code "67") (name "unconnected-(U1A-PB9-Pad46)") (class "Default")
      (node (ref "U1") (pin "46") (pinfunction "PB9_46") (pintype "bidirectional"))
    )
    (net (code "68") (name "unconnected-(U1A-PC13-TAMPER-RTC-Pad2)") (class "Default")
      (node (ref "U1") (pin "2") (pinfunction "PC13-TAMPER-RTC_2") (pintype "bidirectional"))
    )
    (net (code "69") (name "unconnected-(U1A-PC14-OSC32_IN-Pad3)") (class "Default")
      (node (ref "U1") (pin "3") (pinfunction "PC14-OSC32_IN_3") (pintype "bidirectional"))
    )
    (net (code "70") (name "unconnected-(U1A-PC15-OSC32_OUT-Pad4)") (class "Default")
      (node (ref "U1") (pin "4") (pinfunction "PC15-OSC32_OUT_4") (pintype "bidirectional"))
    )
    (net (code "71") (name "unconnected-(U4-EN-Pad2)") (class "Default")
      (node (ref "U4") (pin "2") (pinfunction "EN_2") (pintype "passive"))
    )
    (net (code "72") (name "unconnected-(U6-Vref-Pad5)") (class "Default")
      (node (ref "U6") (pin "5") (pinfunction "Vref_5") (pintype "passive"))
    )
  )
)
